# G1-CM4.net
KiCad netlist of a schematic drawn in Altium Designer
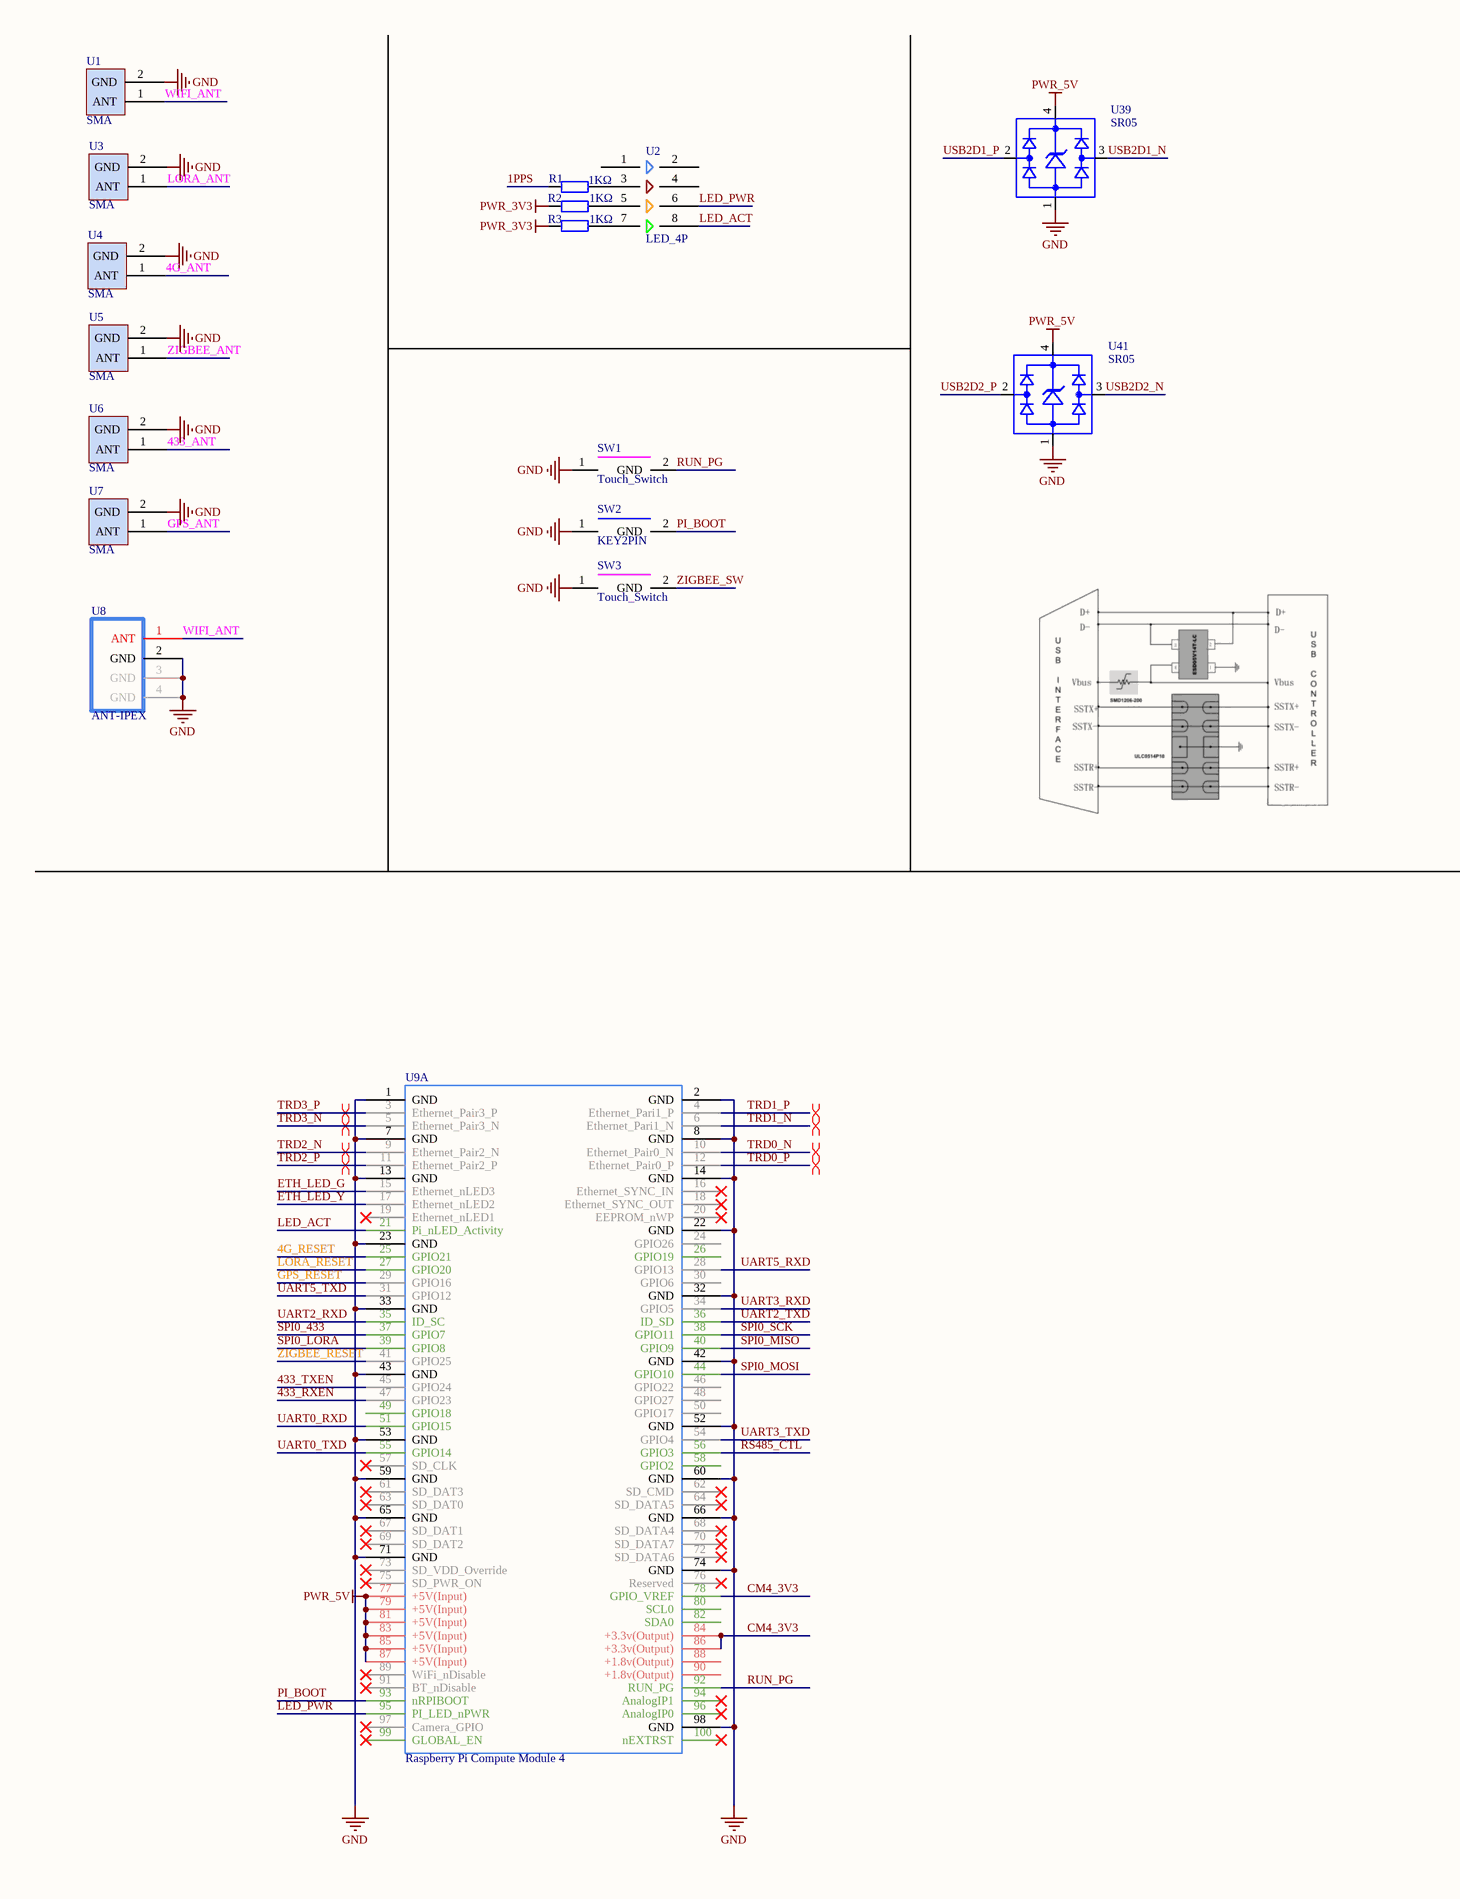
[diagram p0: G1-CM4.SchDoc, left]
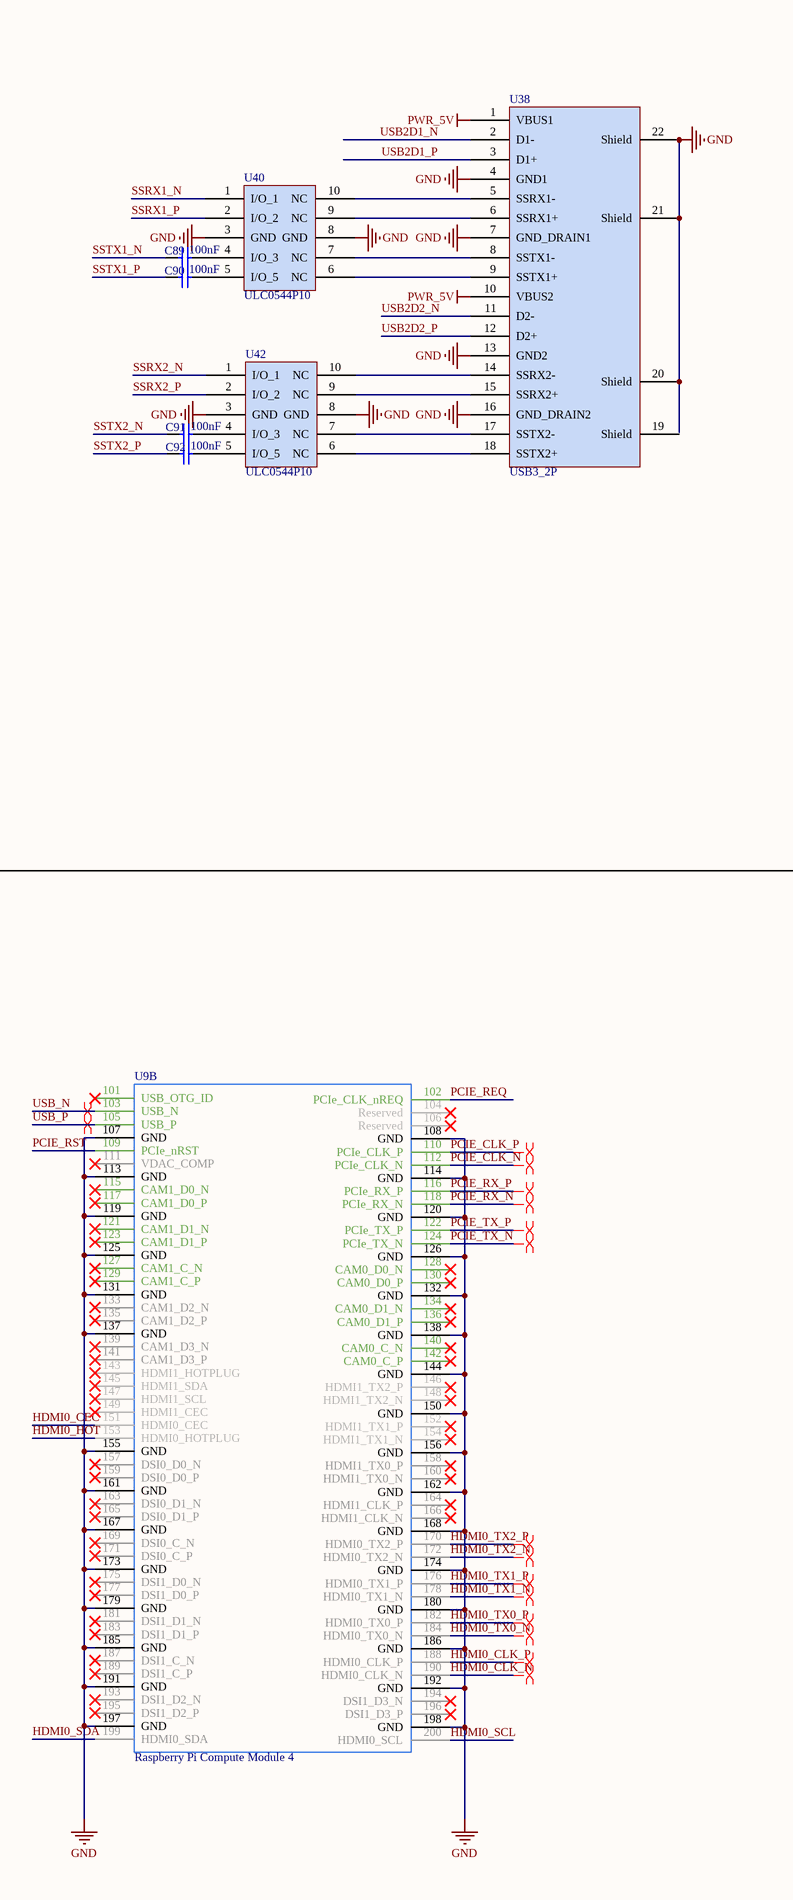
[diagram p1: G1-CM4.SchDoc, right]

(export (version "E")
  (design (tool "Eeschema 10.0.6"))
  (components
    (comp (ref "C89")
      (value "100nF")
      (footprint "0402_C")
      (description "贴片电容")
      (libsource (lib "Miscellaneous Devices LC") (part "0402 100nF (104) 10% 16V"))
    )
    (comp (ref "C90")
      (value "100nF")
      (footprint "0402_C")
      (description "贴片电容")
      (libsource (lib "Miscellaneous Devices LC") (part "0402 100nF (104) 10% 16V"))
    )
    (comp (ref "C91")
      (value "100nF")
      (footprint "0402_C")
      (description "贴片电容")
      (libsource (lib "Miscellaneous Devices LC") (part "0402 100nF (104) 10% 16V"))
    )
    (comp (ref "C92")
      (value "100nF")
      (footprint "0402_C")
      (description "贴片电容")
      (libsource (lib "Miscellaneous Devices LC") (part "0402 100nF (104) 10% 16V"))
    )
    (comp (ref "R1")
      (value "1KΩ")
      (footprint "0402_R")
      (description "贴片电阻")
      (libsource (lib "Miscellaneous Devices LC") (part "0402 1KΩ (1001) 1%"))
    )
    (comp (ref "R2")
      (value "1KΩ")
      (footprint "0402_R")
      (description "贴片电阻")
      (libsource (lib "Miscellaneous Devices LC") (part "0402 1KΩ (1001) 1%"))
    )
    (comp (ref "R3")
      (value "1KΩ")
      (footprint "0402_R")
      (description "贴片电阻")
      (libsource (lib "Miscellaneous Devices LC") (part "0402 1KΩ (1001) 1%"))
    )
    (comp (ref "SW1")
      (value "Touch_Switch")
      (footprint "Touch_Switch")
      (description "Touch_Switch 2PIN")
      (libsource (lib "bohao") (part "Touch_Switch"))
    )
    (comp (ref "SW2")
      (value "KEY2PIN")
      (footprint "KEY2PIN")
      (description "Switch Button")
      (libsource (lib "bohao") (part "KEY2PIN"))
    )
    (comp (ref "SW3")
      (value "Touch_Switch")
      (footprint "Touch_Switch")
      (description "Touch_Switch 2PIN")
      (libsource (lib "bohao") (part "Touch_Switch"))
    )
    (comp (ref "U1")
      (value "SMA")
      (footprint "SMA")
      (description "SMA ANT")
      (libsource (lib "bohao") (part "SMA"))
    )
    (comp (ref "U2")
      (value "LED_4P")
      (footprint "LED_4P")
      (description "LED")
      (libsource (lib "bohao") (part "LED_4P"))
    )
    (comp (ref "U3")
      (value "SMA")
      (footprint "SMA")
      (description "SMA ANT")
      (libsource (lib "bohao") (part "SMA"))
    )
    (comp (ref "U4")
      (value "SMA")
      (footprint "SMA")
      (description "SMA ANT")
      (libsource (lib "bohao") (part "SMA"))
    )
    (comp (ref "U5")
      (value "SMA")
      (footprint "SMA")
      (description "SMA ANT")
      (libsource (lib "bohao") (part "SMA"))
    )
    (comp (ref "U6")
      (value "SMA")
      (footprint "SMA")
      (description "SMA ANT")
      (libsource (lib "bohao") (part "SMA"))
    )
    (comp (ref "U7")
      (value "SMA")
      (footprint "SMA")
      (description "SMA ANT")
      (libsource (lib "bohao") (part "SMA"))
    )
    (comp (ref "U8")
      (value "ANT-IPEX")
      (footprint "ANT-IPEX")
      (description "ANT")
      (libsource (lib "Sensor") (part "ANT-IPEX"))
    )
    (comp (ref "U9")
      (value "Raspberry Pi Compute Module 4")
      (footprint "CM4T-DF40HC(3.0)-100DS")
      (libsource (lib "bohao") (part "CM4"))
    )
    (comp (ref "U38")
      (value "USB3_2P")
      (footprint "USB3_2P")
      (description "USB3.0 2Ports")
      (libsource (lib "bohao") (part "USB3_2P"))
    )
    (comp (ref "U39") (value "SR05") (footprint "SR05") (libsource (lib "bohao") (part "SR05")))
    (comp (ref "U40")
      (value "ULC0544P10")
      (footprint "ULC0544P10")
      (description "ESD")
      (libsource (lib "bohao") (part "ULC0544P10"))
    )
    (comp (ref "U41") (value "SR05") (footprint "SR05") (libsource (lib "bohao") (part "SR05")))
    (comp (ref "U42")
      (value "ULC0544P10")
      (footprint "ULC0544P10")
      (description "ESD")
      (libsource (lib "bohao") (part "ULC0544P10"))
    )
  )
  (nets
    (net (code "1") (name "/1PPS") (class "Default")
      (node (ref "R1") (pin "1") (pinfunction "1_1") (pintype "passive"))
    )
    (net (code "2") (name "/4G_ANT") (class "Default")
      (node (ref "U4") (pin "1") (pinfunction "ANT_1") (pintype "passive"))
    )
    (net (code "3") (name "/4G_RESET") (class "Default")
      (node (ref "U9") (pin "25") (pinfunction "GPIO21_25") (pintype "passive"))
    )
    (net (code "4") (name "/433_ANT") (class "Default")
      (node (ref "U6") (pin "1") (pinfunction "ANT_1") (pintype "passive"))
    )
    (net (code "5") (name "/433_RXEN") (class "Default")
      (node (ref "U9") (pin "47") (pinfunction "GPIO23_47") (pintype "passive"))
    )
    (net (code "6") (name "/433_TXEN") (class "Default")
      (node (ref "U9") (pin "45") (pinfunction "GPIO24_45") (pintype "passive"))
    )
    (net (code "7") (name "/CM4_3V3") (class "Default")
      (node (ref "U9") (pin "78") (pinfunction "GPIO_VREF_78") (pintype "passive"))
      (node (ref "U9") (pin "84") (pinfunction "+3.3v(Output)_84") (pintype "passive"))
      (node (ref "U9") (pin "86") (pinfunction "+3.3v(Output)_86") (pintype "passive"))
    )
    (net (code "8") (name "/ETH_LED_G") (class "Default")
      (node (ref "U9") (pin "15") (pinfunction "Ethernet_nLED3_15") (pintype "passive"))
    )
    (net (code "9") (name "/ETH_LED_Y") (class "Default")
      (node (ref "U9") (pin "17") (pinfunction "Ethernet_nLED2_17") (pintype "passive"))
    )
    (net (code "10") (name "/GPS_ANT") (class "Default")
      (node (ref "U7") (pin "1") (pinfunction "ANT_1") (pintype "passive"))
    )
    (net (code "11") (name "/GPS_RESET") (class "Default")
      (node (ref "U9") (pin "29") (pinfunction "GPIO16_29") (pintype "passive"))
    )
    (net (code "12") (name "/HDMI0_CEC") (class "Default")
      (node (ref "U9") (pin "151") (pinfunction "HDMI0_CEC_151") (pintype "passive"))
    )
    (net (code "13") (name "/HDMI0_CLK_N") (class "Default")
      (node (ref "U9") (pin "190") (pinfunction "HDMI0_CLK_N_190") (pintype "passive"))
    )
    (net (code "14") (name "/HDMI0_CLK_P") (class "Default")
      (node (ref "U9") (pin "188") (pinfunction "HDMI0_CLK_P_188") (pintype "passive"))
    )
    (net (code "15") (name "/HDMI0_HOT") (class "Default")
      (node (ref "U9") (pin "153") (pinfunction "HDMI0_HOTPLUG_153") (pintype "passive"))
    )
    (net (code "16") (name "/HDMI0_SCL") (class "Default")
      (node (ref "U9") (pin "200") (pinfunction "HDMI0_SCL_200") (pintype "passive"))
    )
    (net (code "17") (name "/HDMI0_SDA") (class "Default")
      (node (ref "U9") (pin "199") (pinfunction "HDMI0_SDA_199") (pintype "passive"))
    )
    (net (code "18") (name "/HDMI0_TX0_N") (class "Default")
      (node (ref "U9") (pin "184") (pinfunction "HDMI0_TX0_N_184") (pintype "passive"))
    )
    (net (code "19") (name "/HDMI0_TX0_P") (class "Default")
      (node (ref "U9") (pin "182") (pinfunction "HDMI0_TX0_P_182") (pintype "passive"))
    )
    (net (code "20") (name "/HDMI0_TX1_N") (class "Default")
      (node (ref "U9") (pin "178") (pinfunction "HDMI0_TX1_N_178") (pintype "passive"))
    )
    (net (code "21") (name "/HDMI0_TX1_P") (class "Default")
      (node (ref "U9") (pin "176") (pinfunction "HDMI0_TX1_P_176") (pintype "passive"))
    )
    (net (code "22") (name "/HDMI0_TX2_N") (class "Default")
      (node (ref "U9") (pin "172") (pinfunction "HDMI0_TX2_N_172") (pintype "passive"))
    )
    (net (code "23") (name "/HDMI0_TX2_P") (class "Default")
      (node (ref "U9") (pin "170") (pinfunction "HDMI0_TX2_P_170") (pintype "passive"))
    )
    (net (code "24") (name "/LED_ACT") (class "Default")
      (node (ref "U2") (pin "8") (pintype "passive"))
      (node (ref "U9") (pin "21") (pinfunction "Pi_nLED_Activity_21") (pintype "passive"))
    )
    (net (code "25") (name "/LED_PWR") (class "Default")
      (node (ref "U2") (pin "6") (pintype "passive"))
      (node (ref "U9") (pin "95") (pinfunction "PI_LED_nPWR_95") (pintype "passive"))
    )
    (net (code "26") (name "/LORA_ANT") (class "Default")
      (node (ref "U3") (pin "1") (pinfunction "ANT_1") (pintype "passive"))
    )
    (net (code "27") (name "/LORA_RESET") (class "Default")
      (node (ref "U9") (pin "27") (pinfunction "GPIO20_27") (pintype "passive"))
    )
    (net (code "28") (name "/PCIE_CLK_N") (class "Default")
      (node (ref "U9") (pin "112") (pinfunction "PCIe_CLK_N_112") (pintype "passive"))
    )
    (net (code "29") (name "/PCIE_CLK_P") (class "Default")
      (node (ref "U9") (pin "110") (pinfunction "PCIe_CLK_P_110") (pintype "passive"))
    )
    (net (code "30") (name "/PCIE_REQ") (class "Default")
      (node (ref "U9") (pin "102") (pinfunction "PCIe_CLK_nREQ_102") (pintype "passive"))
    )
    (net (code "31") (name "/PCIE_RST") (class "Default")
      (node (ref "U9") (pin "109") (pinfunction "PCIe_nRST_109") (pintype "passive"))
    )
    (net (code "32") (name "/PCIE_RX_N") (class "Default")
      (node (ref "U9") (pin "118") (pinfunction "PCIe_RX_N_118") (pintype "passive"))
    )
    (net (code "33") (name "/PCIE_RX_P") (class "Default")
      (node (ref "U9") (pin "116") (pinfunction "PCIe_RX_P_116") (pintype "passive"))
    )
    (net (code "34") (name "/PCIE_TX_N") (class "Default")
      (node (ref "U9") (pin "124") (pinfunction "PCIe_TX_N_124") (pintype "passive"))
    )
    (net (code "35") (name "/PCIE_TX_P") (class "Default")
      (node (ref "U9") (pin "122") (pinfunction "PCIe_TX_P_122") (pintype "passive"))
    )
    (net (code "36") (name "/PI_BOOT") (class "Default")
      (node (ref "SW2") (pin "2") (pinfunction "GND_2") (pintype "passive"))
      (node (ref "U9") (pin "93") (pinfunction "nRPIBOOT_93") (pintype "passive"))
    )
    (net (code "37") (name "/RS485_CTL") (class "Default")
      (node (ref "U9") (pin "56") (pinfunction "GPIO3_56") (pintype "passive"))
    )
    (net (code "38") (name "/RUN_PG") (class "Default")
      (node (ref "SW1") (pin "2") (pinfunction "GND_2") (pintype "passive"))
      (node (ref "U9") (pin "92") (pinfunction "RUN_PG_92") (pintype "passive"))
    )
    (net (code "39") (name "/SPI0_433") (class "Default")
      (node (ref "U9") (pin "37") (pinfunction "GPIO7_37") (pintype "passive"))
    )
    (net (code "40") (name "/SPI0_LORA") (class "Default")
      (node (ref "U9") (pin "39") (pinfunction "GPIO8_39") (pintype "passive"))
    )
    (net (code "41") (name "/SPI0_MISO") (class "Default")
      (node (ref "U9") (pin "40") (pinfunction "GPIO9_40") (pintype "passive"))
    )
    (net (code "42") (name "/SPI0_MOSI") (class "Default")
      (node (ref "U9") (pin "44") (pinfunction "GPIO10_44") (pintype "passive"))
    )
    (net (code "43") (name "/SPI0_SCK") (class "Default")
      (node (ref "U9") (pin "38") (pinfunction "GPIO11_38") (pintype "passive"))
    )
    (net (code "44") (name "/SSRX1_N") (class "Default")
      (node (ref "U40") (pin "1") (pinfunction "I/O_1_1") (pintype "passive"))
    )
    (net (code "45") (name "/SSRX1_P") (class "Default")
      (node (ref "U40") (pin "2") (pinfunction "I/O_2_2") (pintype "passive"))
    )
    (net (code "46") (name "/SSRX2_N") (class "Default")
      (node (ref "U42") (pin "1") (pinfunction "I/O_1_1") (pintype "passive"))
    )
    (net (code "47") (name "/SSRX2_P") (class "Default")
      (node (ref "U42") (pin "2") (pinfunction "I/O_2_2") (pintype "passive"))
    )
    (net (code "48") (name "/SSTX1_N") (class "Default")
      (node (ref "C89") (pin "1") (pinfunction "1_1") (pintype "passive"))
    )
    (net (code "49") (name "/SSTX1_P") (class "Default")
      (node (ref "C90") (pin "1") (pinfunction "1_1") (pintype "passive"))
    )
    (net (code "50") (name "/SSTX2_N") (class "Default")
      (node (ref "C91") (pin "1") (pinfunction "1_1") (pintype "passive"))
    )
    (net (code "51") (name "/SSTX2_P") (class "Default")
      (node (ref "C92") (pin "1") (pinfunction "1_1") (pintype "passive"))
    )
    (net (code "52") (name "/TRD0_N") (class "Default")
      (node (ref "U9") (pin "10") (pinfunction "Ethernet_Pair0_N_10") (pintype "passive"))
    )
    (net (code "53") (name "/TRD0_P") (class "Default")
      (node (ref "U9") (pin "12") (pinfunction "Ethernet_Pair0_P_12") (pintype "passive"))
    )
    (net (code "54") (name "/TRD1_N") (class "Default")
      (node (ref "U9") (pin "6") (pinfunction "Ethernet_Pari1_N_6") (pintype "passive"))
    )
    (net (code "55") (name "/TRD1_P") (class "Default")
      (node (ref "U9") (pin "4") (pinfunction "Ethernet_Pari1_P_4") (pintype "passive"))
    )
    (net (code "56") (name "/TRD2_N") (class "Default")
      (node (ref "U9") (pin "9") (pinfunction "Ethernet_Pair2_N_9") (pintype "passive"))
    )
    (net (code "57") (name "/TRD2_P") (class "Default")
      (node (ref "U9") (pin "11") (pinfunction "Ethernet_Pair2_P_11") (pintype "passive"))
    )
    (net (code "58") (name "/TRD3_N") (class "Default")
      (node (ref "U9") (pin "5") (pinfunction "Ethernet_Pair3_N_5") (pintype "passive"))
    )
    (net (code "59") (name "/TRD3_P") (class "Default")
      (node (ref "U9") (pin "3") (pinfunction "Ethernet_Pair3_P_3") (pintype "passive"))
    )
    (net (code "60") (name "/UART0_RXD") (class "Default")
      (node (ref "U9") (pin "51") (pinfunction "GPIO15_51") (pintype "passive"))
    )
    (net (code "61") (name "/UART0_TXD") (class "Default")
      (node (ref "U9") (pin "55") (pinfunction "GPIO14_55") (pintype "passive"))
    )
    (net (code "62") (name "/UART2_RXD") (class "Default")
      (node (ref "U9") (pin "35") (pinfunction "ID_SC_35") (pintype "passive"))
    )
    (net (code "63") (name "/UART2_TXD") (class "Default")
      (node (ref "U9") (pin "36") (pinfunction "ID_SD_36") (pintype "passive"))
    )
    (net (code "64") (name "/UART3_RXD") (class "Default")
      (node (ref "U9") (pin "34") (pinfunction "GPIO5_34") (pintype "passive"))
    )
    (net (code "65") (name "/UART3_TXD") (class "Default")
      (node (ref "U9") (pin "54") (pinfunction "GPIO4_54") (pintype "passive"))
    )
    (net (code "66") (name "/UART5_RXD") (class "Default")
      (node (ref "U9") (pin "28") (pinfunction "GPIO13_28") (pintype "passive"))
    )
    (net (code "67") (name "/UART5_TXD") (class "Default")
      (node (ref "U9") (pin "31") (pinfunction "GPIO12_31") (pintype "passive"))
    )
    (net (code "68") (name "/USB2D1_N") (class "Default")
      (node (ref "U38") (pin "2") (pinfunction "D1-_2") (pintype "passive"))
      (node (ref "U39") (pin "3") (pinfunction "3_3") (pintype "passive"))
    )
    (net (code "69") (name "/USB2D1_P") (class "Default")
      (node (ref "U38") (pin "3") (pinfunction "D1+_3") (pintype "passive"))
      (node (ref "U39") (pin "2") (pinfunction "2_2") (pintype "passive"))
    )
    (net (code "70") (name "/USB2D2_N") (class "Default")
      (node (ref "U38") (pin "11") (pinfunction "D2-_11") (pintype "passive"))
      (node (ref "U41") (pin "3") (pinfunction "3_3") (pintype "passive"))
    )
    (net (code "71") (name "/USB2D2_P") (class "Default")
      (node (ref "U38") (pin "12") (pinfunction "D2+_12") (pintype "passive"))
      (node (ref "U41") (pin "2") (pinfunction "2_2") (pintype "passive"))
    )
    (net (code "72") (name "/USB_N") (class "Default")
      (node (ref "U9") (pin "103") (pinfunction "USB_N_103") (pintype "passive"))
    )
    (net (code "73") (name "/USB_P") (class "Default")
      (node (ref "U9") (pin "105") (pinfunction "USB_P_105") (pintype "passive"))
    )
    (net (code "74") (name "/WIFI_ANT") (class "Default")
      (node (ref "U1") (pin "1") (pinfunction "ANT_1") (pintype "passive"))
      (node (ref "U8") (pin "1") (pinfunction "ANT_1") (pintype "passive"))
    )
    (net (code "75") (name "/ZIGBEE_ANT") (class "Default")
      (node (ref "U5") (pin "1") (pinfunction "ANT_1") (pintype "passive"))
    )
    (net (code "76") (name "/ZIGBEE_RESET") (class "Default")
      (node (ref "U9") (pin "41") (pinfunction "GPIO25_41") (pintype "passive"))
    )
    (net (code "77") (name "/ZIGBEE_SW") (class "Default")
      (node (ref "SW3") (pin "2") (pinfunction "GND_2") (pintype "passive"))
    )
    (net (code "78") (name "GND") (class "Default")
      (node (ref "SW1") (pin "1") (pinfunction "1_1") (pintype "passive"))
      (node (ref "SW2") (pin "1") (pinfunction "1_1") (pintype "passive"))
      (node (ref "SW3") (pin "1") (pinfunction "1_1") (pintype "passive"))
      (node (ref "U1") (pin "2") (pinfunction "GND_2") (pintype "passive"))
      (node (ref "U3") (pin "2") (pinfunction "GND_2") (pintype "passive"))
      (node (ref "U38") (pin "13") (pinfunction "GND2_13") (pintype "passive"))
      (node (ref "U38") (pin "16") (pinfunction "GND_DRAIN2_16") (pintype "passive"))
      (node (ref "U38") (pin "20") (pinfunction "Shield_20") (pintype "passive"))
      (node (ref "U38") (pin "21") (pinfunction "Shield_21") (pintype "passive"))
      (node (ref "U38") (pin "22") (pinfunction "Shield_22") (pintype "passive"))
      (node (ref "U38") (pin "4") (pinfunction "GND1_4") (pintype "passive"))
      (node (ref "U38") (pin "7") (pinfunction "GND_DRAIN1_7") (pintype "passive"))
      (node (ref "U39") (pin "1") (pinfunction "1_1") (pintype "passive"))
      (node (ref "U4") (pin "2") (pinfunction "GND_2") (pintype "passive"))
      (node (ref "U40") (pin "3") (pinfunction "GND_3") (pintype "passive"))
      (node (ref "U40") (pin "8") (pinfunction "GND_8") (pintype "passive"))
      (node (ref "U41") (pin "1") (pinfunction "1_1") (pintype "passive"))
      (node (ref "U42") (pin "3") (pinfunction "GND_3") (pintype "passive"))
      (node (ref "U42") (pin "8") (pinfunction "GND_8") (pintype "passive"))
      (node (ref "U5") (pin "2") (pinfunction "GND_2") (pintype "passive"))
      (node (ref "U6") (pin "2") (pinfunction "GND_2") (pintype "passive"))
      (node (ref "U7") (pin "2") (pinfunction "GND_2") (pintype "passive"))
      (node (ref "U8") (pin "2") (pinfunction "GND_2") (pintype "passive"))
      (node (ref "U8") (pin "3") (pinfunction "GND_3") (pintype "passive"))
      (node (ref "U8") (pin "4") (pinfunction "GND_4") (pintype "passive"))
      (node (ref "U9") (pin "1") (pinfunction "GND_1") (pintype "passive"))
      (node (ref "U9") (pin "107") (pinfunction "GND_107") (pintype "passive"))
      (node (ref "U9") (pin "108") (pinfunction "GND_108") (pintype "passive"))
      (node (ref "U9") (pin "113") (pinfunction "GND_113") (pintype "passive"))
      (node (ref "U9") (pin "114") (pinfunction "GND_114") (pintype "passive"))
      (node (ref "U9") (pin "119") (pinfunction "GND_119") (pintype "passive"))
      (node (ref "U9") (pin "120") (pinfunction "GND_120") (pintype "passive"))
      (node (ref "U9") (pin "125") (pinfunction "GND_125") (pintype "passive"))
      (node (ref "U9") (pin "126") (pinfunction "GND_126") (pintype "passive"))
      (node (ref "U9") (pin "13") (pinfunction "GND_13") (pintype "passive"))
      (node (ref "U9") (pin "131") (pinfunction "GND_131") (pintype "passive"))
      (node (ref "U9") (pin "132") (pinfunction "GND_132") (pintype "passive"))
      (node (ref "U9") (pin "137") (pinfunction "GND_137") (pintype "passive"))
      (node (ref "U9") (pin "138") (pinfunction "GND_138") (pintype "passive"))
      (node (ref "U9") (pin "14") (pinfunction "GND_14") (pintype "passive"))
      (node (ref "U9") (pin "144") (pinfunction "GND_144") (pintype "passive"))
      (node (ref "U9") (pin "150") (pinfunction "GND_150") (pintype "passive"))
      (node (ref "U9") (pin "155") (pinfunction "GND_155") (pintype "passive"))
      (node (ref "U9") (pin "156") (pinfunction "GND_156") (pintype "passive"))
      (node (ref "U9") (pin "161") (pinfunction "GND_161") (pintype "passive"))
      (node (ref "U9") (pin "162") (pinfunction "GND_162") (pintype "passive"))
      (node (ref "U9") (pin "167") (pinfunction "GND_167") (pintype "passive"))
      (node (ref "U9") (pin "168") (pinfunction "GND_168") (pintype "passive"))
      (node (ref "U9") (pin "173") (pinfunction "GND_173") (pintype "passive"))
      (node (ref "U9") (pin "174") (pinfunction "GND_174") (pintype "passive"))
      (node (ref "U9") (pin "179") (pinfunction "GND_179") (pintype "passive"))
      (node (ref "U9") (pin "180") (pinfunction "GND_180") (pintype "passive"))
      (node (ref "U9") (pin "185") (pinfunction "GND_185") (pintype "passive"))
      (node (ref "U9") (pin "186") (pinfunction "GND_186") (pintype "passive"))
      (node (ref "U9") (pin "191") (pinfunction "GND_191") (pintype "passive"))
      (node (ref "U9") (pin "192") (pinfunction "GND_192") (pintype "passive"))
      (node (ref "U9") (pin "197") (pinfunction "GND_197") (pintype "passive"))
      (node (ref "U9") (pin "198") (pinfunction "GND_198") (pintype "passive"))
      (node (ref "U9") (pin "2") (pinfunction "GND_2") (pintype "passive"))
      (node (ref "U9") (pin "22") (pinfunction "GND_22") (pintype "passive"))
      (node (ref "U9") (pin "23") (pinfunction "GND_23") (pintype "passive"))
      (node (ref "U9") (pin "32") (pinfunction "GND_32") (pintype "passive"))
      (node (ref "U9") (pin "33") (pinfunction "GND_33") (pintype "passive"))
      (node (ref "U9") (pin "42") (pinfunction "GND_42") (pintype "passive"))
      (node (ref "U9") (pin "43") (pinfunction "GND_43") (pintype "passive"))
      (node (ref "U9") (pin "52") (pinfunction "GND_52") (pintype "passive"))
      (node (ref "U9") (pin "53") (pinfunction "GND_53") (pintype "passive"))
      (node (ref "U9") (pin "59") (pinfunction "GND_59") (pintype "passive"))
      (node (ref "U9") (pin "60") (pinfunction "GND_60") (pintype "passive"))
      (node (ref "U9") (pin "65") (pinfunction "GND_65") (pintype "passive"))
      (node (ref "U9") (pin "66") (pinfunction "GND_66") (pintype "passive"))
      (node (ref "U9") (pin "7") (pinfunction "GND_7") (pintype "passive"))
      (node (ref "U9") (pin "71") (pinfunction "GND_71") (pintype "passive"))
      (node (ref "U9") (pin "74") (pinfunction "GND_74") (pintype "passive"))
      (node (ref "U9") (pin "8") (pinfunction "GND_8") (pintype "passive"))
      (node (ref "U9") (pin "98") (pinfunction "GND_98") (pintype "passive"))
    )
    (net (code "79") (name "Net-(R1-Pad2)") (class "Default")
      (node (ref "R1") (pin "2") (pinfunction "2_2") (pintype "passive"))
      (node (ref "U2") (pin "3") (pintype "passive"))
    )
    (net (code "80") (name "Net-(R2-Pad2)") (class "Default")
      (node (ref "R2") (pin "2") (pinfunction "2_2") (pintype "passive"))
      (node (ref "U2") (pin "5") (pintype "passive"))
    )
    (net (code "81") (name "Net-(R3-Pad2)") (class "Default")
      (node (ref "R3") (pin "2") (pinfunction "2_2") (pintype "passive"))
      (node (ref "U2") (pin "7") (pintype "passive"))
    )
    (net (code "82") (name "Net-(U38-SSRX1+)") (class "Default")
      (node (ref "U38") (pin "6") (pinfunction "SSRX1+_6") (pintype "passive"))
      (node (ref "U40") (pin "9") (pinfunction "NC_9") (pintype "passive"))
    )
    (net (code "83") (name "Net-(U38-SSRX1-)") (class "Default")
      (node (ref "U38") (pin "5") (pinfunction "SSRX1-_5") (pintype "passive"))
      (node (ref "U40") (pin "10") (pinfunction "NC_10") (pintype "passive"))
    )
    (net (code "84") (name "Net-(U38-SSRX2+)") (class "Default")
      (node (ref "U38") (pin "15") (pinfunction "SSRX2+_15") (pintype "passive"))
      (node (ref "U42") (pin "9") (pinfunction "NC_9") (pintype "passive"))
    )
    (net (code "85") (name "Net-(U38-SSRX2-)") (class "Default")
      (node (ref "U38") (pin "14") (pinfunction "SSRX2-_14") (pintype "passive"))
      (node (ref "U42") (pin "10") (pinfunction "NC_10") (pintype "passive"))
    )
    (net (code "86") (name "Net-(U38-SSTX1+)") (class "Default")
      (node (ref "U38") (pin "9") (pinfunction "SSTX1+_9") (pintype "passive"))
      (node (ref "U40") (pin "6") (pinfunction "NC_6") (pintype "passive"))
    )
    (net (code "87") (name "Net-(U38-SSTX1-)") (class "Default")
      (node (ref "U38") (pin "8") (pinfunction "SSTX1-_8") (pintype "passive"))
      (node (ref "U40") (pin "7") (pinfunction "NC_7") (pintype "passive"))
    )
    (net (code "88") (name "Net-(U38-SSTX2+)") (class "Default")
      (node (ref "U38") (pin "18") (pinfunction "SSTX2+_18") (pintype "passive"))
      (node (ref "U42") (pin "6") (pinfunction "NC_6") (pintype "passive"))
    )
    (net (code "89") (name "Net-(U38-SSTX2-)") (class "Default")
      (node (ref "U38") (pin "17") (pinfunction "SSTX2-_17") (pintype "passive"))
      (node (ref "U42") (pin "7") (pinfunction "NC_7") (pintype "passive"))
    )
    (net (code "90") (name "Net-(U40-I{slash}O_3)") (class "Default")
      (node (ref "C89") (pin "2") (pinfunction "2_2") (pintype "passive"))
      (node (ref "U40") (pin "4") (pinfunction "I/O_3_4") (pintype "passive"))
    )
    (net (code "91") (name "Net-(U40-I{slash}O_5)") (class "Default")
      (node (ref "C90") (pin "2") (pinfunction "2_2") (pintype "passive"))
      (node (ref "U40") (pin "5") (pinfunction "I/O_5_5") (pintype "passive"))
    )
    (net (code "92") (name "Net-(U42-I{slash}O_3)") (class "Default")
      (node (ref "C91") (pin "2") (pinfunction "2_2") (pintype "passive"))
      (node (ref "U42") (pin "4") (pinfunction "I/O_3_4") (pintype "passive"))
    )
    (net (code "93") (name "Net-(U42-I{slash}O_5)") (class "Default")
      (node (ref "C92") (pin "2") (pinfunction "2_2") (pintype "passive"))
      (node (ref "U42") (pin "5") (pinfunction "I/O_5_5") (pintype "passive"))
    )
    (net (code "94") (name "PWR_3V3") (class "Default")
      (node (ref "R2") (pin "1") (pinfunction "1_1") (pintype "passive"))
      (node (ref "R3") (pin "1") (pinfunction "1_1") (pintype "passive"))
    )
    (net (code "95") (name "PWR_5V") (class "Default")
      (node (ref "U38") (pin "1") (pinfunction "VBUS1_1") (pintype "passive"))
      (node (ref "U38") (pin "10") (pinfunction "VBUS2_10") (pintype "passive"))
      (node (ref "U39") (pin "4") (pinfunction "4_4") (pintype "passive"))
      (node (ref "U41") (pin "4") (pinfunction "4_4") (pintype "passive"))
      (node (ref "U9") (pin "77") (pinfunction "+5V(Input)_77") (pintype "passive"))
      (node (ref "U9") (pin "79") (pinfunction "+5V(Input)_79") (pintype "passive"))
      (node (ref "U9") (pin "81") (pinfunction "+5V(Input)_81") (pintype "passive"))
      (node (ref "U9") (pin "83") (pinfunction "+5V(Input)_83") (pintype "passive"))
      (node (ref "U9") (pin "85") (pinfunction "+5V(Input)_85") (pintype "passive"))
      (node (ref "U9") (pin "87") (pinfunction "+5V(Input)_87") (pintype "passive"))
    )
    (net (code "96") (name "unconnected-(U2-Pad1)") (class "Default")
      (node (ref "U2") (pin "1") (pintype "passive"))
    )
    (net (code "97") (name "unconnected-(U2-Pad2)") (class "Default")
      (node (ref "U2") (pin "2") (pintype "passive"))
    )
    (net (code "98") (name "unconnected-(U2-Pad4)") (class "Default")
      (node (ref "U2") (pin "4") (pintype "passive"))
    )
    (net (code "99") (name "unconnected-(U9A-+1.8v(Output)-Pad88)") (class "Default")
      (node (ref "U9") (pin "88") (pinfunction "+1.8v(Output)_88") (pintype "passive"))
    )
    (net (code "100") (name "unconnected-(U9A-+1.8v(Output)-Pad90)") (class "Default")
      (node (ref "U9") (pin "90") (pinfunction "+1.8v(Output)_90") (pintype "passive"))
    )
    (net (code "101") (name "unconnected-(U9A-AnalogIP0-Pad96)") (class "Default")
      (node (ref "U9") (pin "96") (pinfunction "AnalogIP0_96") (pintype "passive+no_connect"))
    )
    (net (code "102") (name "unconnected-(U9A-AnalogIP1-Pad94)") (class "Default")
      (node (ref "U9") (pin "94") (pinfunction "AnalogIP1_94") (pintype "passive+no_connect"))
    )
    (net (code "103") (name "unconnected-(U9A-BT_nDisable-Pad91)") (class "Default")
      (node (ref "U9") (pin "91") (pinfunction "BT_nDisable_91") (pintype "passive+no_connect"))
    )
    (net (code "104") (name "unconnected-(U9A-Camera_GPIO-Pad97)") (class "Default")
      (node (ref "U9") (pin "97") (pinfunction "Camera_GPIO_97") (pintype "passive+no_connect"))
    )
    (net (code "105") (name "unconnected-(U9A-EEPROM_nWP-Pad20)") (class "Default")
      (node (ref "U9") (pin "20") (pinfunction "EEPROM_nWP_20") (pintype "passive+no_connect"))
    )
    (net (code "106") (name "unconnected-(U9A-Ethernet_SYNC_IN-Pad16)") (class "Default")
      (node (ref "U9") (pin "16") (pinfunction "Ethernet_SYNC_IN_16") (pintype "passive+no_connect"))
    )
    (net (code "107") (name "unconnected-(U9A-Ethernet_SYNC_OUT-Pad18)") (class "Default")
      (node (ref "U9") (pin "18") (pinfunction "Ethernet_SYNC_OUT_18") (pintype "passive+no_connect"))
    )
    (net (code "108") (name "unconnected-(U9A-Ethernet_nLED1-Pad19)") (class "Default")
      (node (ref "U9") (pin "19") (pinfunction "Ethernet_nLED1_19") (pintype "passive+no_connect"))
    )
    (net (code "109") (name "unconnected-(U9A-GLOBAL_EN-Pad99)") (class "Default")
      (node (ref "U9") (pin "99") (pinfunction "GLOBAL_EN_99") (pintype "passive+no_connect"))
    )
    (net (code "110") (name "unconnected-(U9A-GPIO2-Pad58)") (class "Default")
      (node (ref "U9") (pin "58") (pinfunction "GPIO2_58") (pintype "passive"))
    )
    (net (code "111") (name "unconnected-(U9A-GPIO6-Pad30)") (class "Default")
      (node (ref "U9") (pin "30") (pinfunction "GPIO6_30") (pintype "passive"))
    )
    (net (code "112") (name "unconnected-(U9A-GPIO17-Pad50)") (class "Default")
      (node (ref "U9") (pin "50") (pinfunction "GPIO17_50") (pintype "passive"))
    )
    (net (code "113") (name "unconnected-(U9A-GPIO18-Pad49)") (class "Default")
      (node (ref "U9") (pin "49") (pinfunction "GPIO18_49") (pintype "passive"))
    )
    (net (code "114") (name "unconnected-(U9A-GPIO19-Pad26)") (class "Default")
      (node (ref "U9") (pin "26") (pinfunction "GPIO19_26") (pintype "passive"))
    )
    (net (code "115") (name "unconnected-(U9A-GPIO22-Pad46)") (class "Default")
      (node (ref "U9") (pin "46") (pinfunction "GPIO22_46") (pintype "passive"))
    )
    (net (code "116") (name "unconnected-(U9A-GPIO26-Pad24)") (class "Default")
      (node (ref "U9") (pin "24") (pinfunction "GPIO26_24") (pintype "passive"))
    )
    (net (code "117") (name "unconnected-(U9A-GPIO27-Pad48)") (class "Default")
      (node (ref "U9") (pin "48") (pinfunction "GPIO27_48") (pintype "passive"))
    )
    (net (code "118") (name "unconnected-(U9A-Reserved-Pad76)") (class "Default")
      (node (ref "U9") (pin "76") (pinfunction "Reserved_76") (pintype "passive+no_connect"))
    )
    (net (code "119") (name "unconnected-(U9A-SCL0-Pad80)") (class "Default")
      (node (ref "U9") (pin "80") (pinfunction "SCL0_80") (pintype "passive"))
    )
    (net (code "120") (name "unconnected-(U9A-SDA0-Pad82)") (class "Default")
      (node (ref "U9") (pin "82") (pinfunction "SDA0_82") (pintype "passive"))
    )
    (net (code "121") (name "unconnected-(U9A-SD_CLK-Pad57)") (class "Default")
      (node (ref "U9") (pin "57") (pinfunction "SD_CLK_57") (pintype "passive+no_connect"))
    )
    (net (code "122") (name "unconnected-(U9A-SD_CMD-Pad62)") (class "Default")
      (node (ref "U9") (pin "62") (pinfunction "SD_CMD_62") (pintype "passive+no_connect"))
    )
    (net (code "123") (name "unconnected-(U9A-SD_DAT0-Pad63)") (class "Default")
      (node (ref "U9") (pin "63") (pinfunction "SD_DAT0_63") (pintype "passive+no_connect"))
    )
    (net (code "124") (name "unconnected-(U9A-SD_DAT1-Pad67)") (class "Default")
      (node (ref "U9") (pin "67") (pinfunction "SD_DAT1_67") (pintype "passive+no_connect"))
    )
    (net (code "125") (name "unconnected-(U9A-SD_DAT2-Pad69)") (class "Default")
      (node (ref "U9") (pin "69") (pinfunction "SD_DAT2_69") (pintype "passive+no_connect"))
    )
    (net (code "126") (name "unconnected-(U9A-SD_DAT3-Pad61)") (class "Default")
      (node (ref "U9") (pin "61") (pinfunction "SD_DAT3_61") (pintype "passive+no_connect"))
    )
    (net (code "127") (name "unconnected-(U9A-SD_DATA4-Pad68)") (class "Default")
      (node (ref "U9") (pin "68") (pinfunction "SD_DATA4_68") (pintype "passive+no_connect"))
    )
    (net (code "128") (name "unconnected-(U9A-SD_DATA5-Pad64)") (class "Default")
      (node (ref "U9") (pin "64") (pinfunction "SD_DATA5_64") (pintype "passive+no_connect"))
    )
    (net (code "129") (name "unconnected-(U9A-SD_DATA6-Pad72)") (class "Default")
      (node (ref "U9") (pin "72") (pinfunction "SD_DATA6_72") (pintype "passive+no_connect"))
    )
    (net (code "130") (name "unconnected-(U9A-SD_DATA7-Pad70)") (class "Default")
      (node (ref "U9") (pin "70") (pinfunction "SD_DATA7_70") (pintype "passive+no_connect"))
    )
    (net (code "131") (name "unconnected-(U9A-SD_PWR_ON-Pad75)") (class "Default")
      (node (ref "U9") (pin "75") (pinfunction "SD_PWR_ON_75") (pintype "passive+no_connect"))
    )
    (net (code "132") (name "unconnected-(U9A-SD_VDD_Override-Pad73)") (class "Default")
      (node (ref "U9") (pin "73") (pinfunction "SD_VDD_Override_73") (pintype "passive+no_connect"))
    )
    (net (code "133") (name "unconnected-(U9A-WiFi_nDisable-Pad89)") (class "Default")
      (node (ref "U9") (pin "89") (pinfunction "WiFi_nDisable_89") (pintype "passive+no_connect"))
    )
    (net (code "134") (name "unconnected-(U9A-nEXTRST-Pad100)") (class "Default")
      (node (ref "U9") (pin "100") (pinfunction "nEXTRST_100") (pintype "passive+no_connect"))
    )
    (net (code "135") (name "unconnected-(U9B-CAM0_C_N-Pad140)") (class "Default")
      (node (ref "U9") (pin "140") (pinfunction "CAM0_C_N_140") (pintype "passive+no_connect"))
    )
    (net (code "136") (name "unconnected-(U9B-CAM0_C_P-Pad142)") (class "Default")
      (node (ref "U9") (pin "142") (pinfunction "CAM0_C_P_142") (pintype "passive+no_connect"))
    )
    (net (code "137") (name "unconnected-(U9B-CAM0_D0_N-Pad128)") (class "Default")
      (node (ref "U9") (pin "128") (pinfunction "CAM0_D0_N_128") (pintype "passive+no_connect"))
    )
    (net (code "138") (name "unconnected-(U9B-CAM0_D0_P-Pad130)") (class "Default")
      (node (ref "U9") (pin "130") (pinfunction "CAM0_D0_P_130") (pintype "passive+no_connect"))
    )
    (net (code "139") (name "unconnected-(U9B-CAM0_D1_N-Pad134)") (class "Default")
      (node (ref "U9") (pin "134") (pinfunction "CAM0_D1_N_134") (pintype "passive+no_connect"))
    )
    (net (code "140") (name "unconnected-(U9B-CAM0_D1_P-Pad136)") (class "Default")
      (node (ref "U9") (pin "136") (pinfunction "CAM0_D1_P_136") (pintype "passive+no_connect"))
    )
    (net (code "141") (name "unconnected-(U9B-CAM1_C_N-Pad127)") (class "Default")
      (node (ref "U9") (pin "127") (pinfunction "CAM1_C_N_127") (pintype "passive+no_connect"))
    )
    (net (code "142") (name "unconnected-(U9B-CAM1_C_P-Pad129)") (class "Default")
      (node (ref "U9") (pin "129") (pinfunction "CAM1_C_P_129") (pintype "passive+no_connect"))
    )
    (net (code "143") (name "unconnected-(U9B-CAM1_D0_N-Pad115)") (class "Default")
      (node (ref "U9") (pin "115") (pinfunction "CAM1_D0_N_115") (pintype "passive+no_connect"))
    )
    (net (code "144") (name "unconnected-(U9B-CAM1_D0_P-Pad117)") (class "Default")
      (node (ref "U9") (pin "117") (pinfunction "CAM1_D0_P_117") (pintype "passive+no_connect"))
    )
    (net (code "145") (name "unconnected-(U9B-CAM1_D1_N-Pad121)") (class "Default")
      (node (ref "U9") (pin "121") (pinfunction "CAM1_D1_N_121") (pintype "passive+no_connect"))
    )
    (net (code "146") (name "unconnected-(U9B-CAM1_D1_P-Pad123)") (class "Default")
      (node (ref "U9") (pin "123") (pinfunction "CAM1_D1_P_123") (pintype "passive+no_connect"))
    )
    (net (code "147") (name "unconnected-(U9B-CAM1_D2_N-Pad133)") (class "Default")
      (node (ref "U9") (pin "133") (pinfunction "CAM1_D2_N_133") (pintype "passive+no_connect"))
    )
    (net (code "148") (name "unconnected-(U9B-CAM1_D2_P-Pad135)") (class "Default")
      (node (ref "U9") (pin "135") (pinfunction "CAM1_D2_P_135") (pintype "passive+no_connect"))
    )
    (net (code "149") (name "unconnected-(U9B-CAM1_D3_N-Pad139)") (class "Default")
      (node (ref "U9") (pin "139") (pinfunction "CAM1_D3_N_139") (pintype "passive+no_connect"))
    )
    (net (code "150") (name "unconnected-(U9B-CAM1_D3_P-Pad141)") (class "Default")
      (node (ref "U9") (pin "141") (pinfunction "CAM1_D3_P_141") (pintype "passive+no_connect"))
    )
    (net (code "151") (name "unconnected-(U9B-DSI0_C_N-Pad169)") (class "Default")
      (node (ref "U9") (pin "169") (pinfunction "DSI0_C_N_169") (pintype "passive+no_connect"))
    )
    (net (code "152") (name "unconnected-(U9B-DSI0_C_P-Pad171)") (class "Default")
      (node (ref "U9") (pin "171") (pinfunction "DSI0_C_P_171") (pintype "passive+no_connect"))
    )
    (net (code "153") (name "unconnected-(U9B-DSI0_D0_N-Pad157)") (class "Default")
      (node (ref "U9") (pin "157") (pinfunction "DSI0_D0_N_157") (pintype "passive+no_connect"))
    )
    (net (code "154") (name "unconnected-(U9B-DSI0_D0_P-Pad159)") (class "Default")
      (node (ref "U9") (pin "159") (pinfunction "DSI0_D0_P_159") (pintype "passive+no_connect"))
    )
    (net (code "155") (name "unconnected-(U9B-DSI0_D1_N-Pad163)") (class "Default")
      (node (ref "U9") (pin "163") (pinfunction "DSI0_D1_N_163") (pintype "passive+no_connect"))
    )
    (net (code "156") (name "unconnected-(U9B-DSI0_D1_P-Pad165)") (class "Default")
      (node (ref "U9") (pin "165") (pinfunction "DSI0_D1_P_165") (pintype "passive+no_connect"))
    )
    (net (code "157") (name "unconnected-(U9B-DSI1_C_N-Pad187)") (class "Default")
      (node (ref "U9") (pin "187") (pinfunction "DSI1_C_N_187") (pintype "passive+no_connect"))
    )
    (net (code "158") (name "unconnected-(U9B-DSI1_C_P-Pad189)") (class "Default")
      (node (ref "U9") (pin "189") (pinfunction "DSI1_C_P_189") (pintype "passive+no_connect"))
    )
    (net (code "159") (name "unconnected-(U9B-DSI1_D0_N-Pad175)") (class "Default")
      (node (ref "U9") (pin "175") (pinfunction "DSI1_D0_N_175") (pintype "passive+no_connect"))
    )
    (net (code "160") (name "unconnected-(U9B-DSI1_D0_P-Pad177)") (class "Default")
      (node (ref "U9") (pin "177") (pinfunction "DSI1_D0_P_177") (pintype "passive+no_connect"))
    )
    (net (code "161") (name "unconnected-(U9B-DSI1_D1_N-Pad181)") (class "Default")
      (node (ref "U9") (pin "181") (pinfunction "DSI1_D1_N_181") (pintype "passive+no_connect"))
    )
    (net (code "162") (name "unconnected-(U9B-DSI1_D1_P-Pad183)") (class "Default")
      (node (ref "U9") (pin "183") (pinfunction "DSI1_D1_P_183") (pintype "passive+no_connect"))
    )
    (net (code "163") (name "unconnected-(U9B-DSI1_D2_N-Pad193)") (class "Default")
      (node (ref "U9") (pin "193") (pinfunction "DSI1_D2_N_193") (pintype "passive+no_connect"))
    )
    (net (code "164") (name "unconnected-(U9B-DSI1_D2_P-Pad195)") (class "Default")
      (node (ref "U9") (pin "195") (pinfunction "DSI1_D2_P_195") (pintype "passive+no_connect"))
    )
    (net (code "165") (name "unconnected-(U9B-DSI1_D3_N-Pad194)") (class "Default")
      (node (ref "U9") (pin "194") (pinfunction "DSI1_D3_N_194") (pintype "passive+no_connect"))
    )
    (net (code "166") (name "unconnected-(U9B-DSI1_D3_P-Pad196)") (class "Default")
      (node (ref "U9") (pin "196") (pinfunction "DSI1_D3_P_196") (pintype "passive+no_connect"))
    )
    (net (code "167") (name "unconnected-(U9B-HDMI1_CEC-Pad149)") (class "Default")
      (node (ref "U9") (pin "149") (pinfunction "HDMI1_CEC_149") (pintype "passive+no_connect"))
    )
    (net (code "168") (name "unconnected-(U9B-HDMI1_CLK_N-Pad166)") (class "Default")
      (node (ref "U9") (pin "166") (pinfunction "HDMI1_CLK_N_166") (pintype "passive+no_connect"))
    )
    (net (code "169") (name "unconnected-(U9B-HDMI1_CLK_P-Pad164)") (class "Default")
      (node (ref "U9") (pin "164") (pinfunction "HDMI1_CLK_P_164") (pintype "passive+no_connect"))
    )
    (net (code "170") (name "unconnected-(U9B-HDMI1_HOTPLUG-Pad143)") (class "Default")
      (node (ref "U9") (pin "143") (pinfunction "HDMI1_HOTPLUG_143") (pintype "passive+no_connect"))
    )
    (net (code "171") (name "unconnected-(U9B-HDMI1_SCL-Pad147)") (class "Default")
      (node (ref "U9") (pin "147") (pinfunction "HDMI1_SCL_147") (pintype "passive+no_connect"))
    )
    (net (code "172") (name "unconnected-(U9B-HDMI1_SDA-Pad145)") (class "Default")
      (node (ref "U9") (pin "145") (pinfunction "HDMI1_SDA_145") (pintype "passive+no_connect"))
    )
    (net (code "173") (name "unconnected-(U9B-HDMI1_TX0_N-Pad160)") (class "Default")
      (node (ref "U9") (pin "160") (pinfunction "HDMI1_TX0_N_160") (pintype "passive+no_connect"))
    )
    (net (code "174") (name "unconnected-(U9B-HDMI1_TX0_P-Pad158)") (class "Default")
      (node (ref "U9") (pin "158") (pinfunction "HDMI1_TX0_P_158") (pintype "passive+no_connect"))
    )
    (net (code "175") (name "unconnected-(U9B-HDMI1_TX1_N-Pad154)") (class "Default")
      (node (ref "U9") (pin "154") (pinfunction "HDMI1_TX1_N_154") (pintype "passive+no_connect"))
    )
    (net (code "176") (name "unconnected-(U9B-HDMI1_TX1_P-Pad152)") (class "Default")
      (node (ref "U9") (pin "152") (pinfunction "HDMI1_TX1_P_152") (pintype "passive+no_connect"))
    )
    (net (code "177") (name "unconnected-(U9B-HDMI1_TX2_N-Pad148)") (class "Default")
      (node (ref "U9") (pin "148") (pinfunction "HDMI1_TX2_N_148") (pintype "passive+no_connect"))
    )
    (net (code "178") (name "unconnected-(U9B-HDMI1_TX2_P-Pad146)") (class "Default")
      (node (ref "U9") (pin "146") (pinfunction "HDMI1_TX2_P_146") (pintype "passive+no_connect"))
    )
    (net (code "179") (name "unconnected-(U9B-Reserved-Pad104)") (class "Default")
      (node (ref "U9") (pin "104") (pinfunction "Reserved_104") (pintype "passive+no_connect"))
    )
    (net (code "180") (name "unconnected-(U9B-Reserved-Pad106)") (class "Default")
      (node (ref "U9") (pin "106") (pinfunction "Reserved_106") (pintype "passive+no_connect"))
    )
    (net (code "181") (name "unconnected-(U9B-USB_OTG_ID-Pad101)") (class "Default")
      (node (ref "U9") (pin "101") (pinfunction "USB_OTG_ID_101") (pintype "passive+no_connect"))
    )
    (net (code "182") (name "unconnected-(U9B-VDAC_COMP-Pad111)") (class "Default")
      (node (ref "U9") (pin "111") (pinfunction "VDAC_COMP_111") (pintype "passive+no_connect"))
    )
    (net (code "183") (name "unconnected-(U38-Shield-Pad19)") (class "Default")
      (node (ref "U38") (pin "19") (pinfunction "Shield_19") (pintype "passive"))
    )
  )
)
